# mm5823.net
KiCad netlist of a schematic drawn in EAGLE
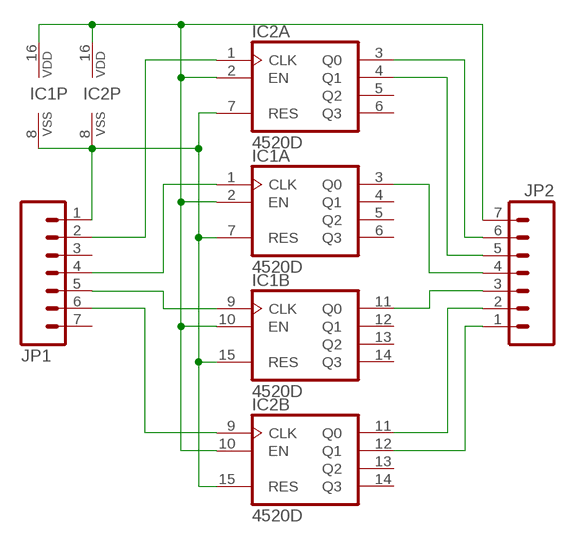
[diagram p0: schematic, sheet 1]

(export (version "E")
  (design (tool "Eeschema 10.0.6"))
  (components
    (comp (ref "IC1")
      (value "4520D")
      (footprint "eagle-import:SO16")
      (libsource (lib "eagle-import") (part "4520D"))
    )
    (comp (ref "IC2")
      (value "4520D")
      (footprint "eagle-import:SO16")
      (libsource (lib "eagle-import") (part "4520D"))
    )
    (comp (ref "JP1")
      (value "M07")
      (footprint "eagle-import:1X07")
      (libsource (lib "eagle-import") (part "M07"))
    )
    (comp (ref "JP2")
      (value "M07")
      (footprint "eagle-import:1X07")
      (libsource (lib "eagle-import") (part "M07"))
    )
  )
  (nets
    (net (code "1") (name "Net-(IC1A-CLK)") (class "Default")
      (node (ref "IC1") (pin "1") (pinfunction "CLK_1") (pintype "input"))
      (node (ref "JP1") (pin "4") (pinfunction "4_4") (pintype "passive"))
    )
    (net (code "2") (name "Net-(IC1A-EN)") (class "Default")
      (node (ref "IC1") (pin "10") (pinfunction "EN_10") (pintype "input"))
      (node (ref "IC1") (pin "16") (pinfunction "VDD_16") (pintype "power_in"))
      (node (ref "IC1") (pin "2") (pinfunction "EN_2") (pintype "input"))
      (node (ref "IC2") (pin "10") (pinfunction "EN_10") (pintype "input"))
      (node (ref "IC2") (pin "16") (pinfunction "VDD_16") (pintype "power_in"))
      (node (ref "IC2") (pin "2") (pinfunction "EN_2") (pintype "input"))
      (node (ref "JP2") (pin "7") (pinfunction "7_7") (pintype "passive"))
    )
    (net (code "3") (name "Net-(IC1A-Q0)") (class "Default")
      (node (ref "IC1") (pin "3") (pinfunction "Q0_3") (pintype "output"))
      (node (ref "JP2") (pin "4") (pinfunction "4_4") (pintype "passive"))
    )
    (net (code "4") (name "Net-(IC1A-RES)") (class "Default")
      (node (ref "IC1") (pin "15") (pinfunction "RES_15") (pintype "input"))
      (node (ref "IC1") (pin "7") (pinfunction "RES_7") (pintype "input"))
      (node (ref "IC1") (pin "8") (pinfunction "VSS_8") (pintype "power_in"))
      (node (ref "IC2") (pin "15") (pinfunction "RES_15") (pintype "input"))
      (node (ref "IC2") (pin "7") (pinfunction "RES_7") (pintype "input"))
      (node (ref "IC2") (pin "8") (pinfunction "VSS_8") (pintype "power_in"))
      (node (ref "JP1") (pin "1") (pinfunction "1_1") (pintype "passive"))
    )
    (net (code "5") (name "Net-(IC1B-CLK)") (class "Default")
      (node (ref "IC1") (pin "9") (pinfunction "CLK_9") (pintype "input"))
      (node (ref "JP1") (pin "5") (pinfunction "5_5") (pintype "passive"))
    )
    (net (code "6") (name "Net-(IC1B-Q0)") (class "Default")
      (node (ref "IC1") (pin "11") (pinfunction "Q0_11") (pintype "output"))
      (node (ref "JP2") (pin "3") (pinfunction "3_3") (pintype "passive"))
    )
    (net (code "7") (name "Net-(IC2A-CLK)") (class "Default")
      (node (ref "IC2") (pin "1") (pinfunction "CLK_1") (pintype "input"))
      (node (ref "JP1") (pin "2") (pinfunction "2_2") (pintype "passive"))
    )
    (net (code "8") (name "Net-(IC2A-Q0)") (class "Default")
      (node (ref "IC2") (pin "3") (pinfunction "Q0_3") (pintype "output"))
      (node (ref "JP2") (pin "6") (pinfunction "6_6") (pintype "passive"))
    )
    (net (code "9") (name "Net-(IC2A-Q1)") (class "Default")
      (node (ref "IC2") (pin "4") (pinfunction "Q1_4") (pintype "output"))
      (node (ref "JP2") (pin "5") (pinfunction "5_5") (pintype "passive"))
    )
    (net (code "10") (name "Net-(IC2B-CLK)") (class "Default")
      (node (ref "IC2") (pin "9") (pinfunction "CLK_9") (pintype "input"))
      (node (ref "JP1") (pin "6") (pinfunction "6_6") (pintype "passive"))
    )
    (net (code "11") (name "Net-(IC2B-Q0)") (class "Default")
      (node (ref "IC2") (pin "11") (pinfunction "Q0_11") (pintype "output"))
      (node (ref "JP2") (pin "2") (pinfunction "2_2") (pintype "passive"))
    )
    (net (code "12") (name "Net-(IC2B-Q1)") (class "Default")
      (node (ref "IC2") (pin "12") (pinfunction "Q1_12") (pintype "output"))
      (node (ref "JP2") (pin "1") (pinfunction "1_1") (pintype "passive"))
    )
    (net (code "13") (name "unconnected-(IC1A-Q1-Pad4)") (class "Default")
      (node (ref "IC1") (pin "4") (pinfunction "Q1_4") (pintype "output"))
    )
    (net (code "14") (name "unconnected-(IC1A-Q2-Pad5)") (class "Default")
      (node (ref "IC1") (pin "5") (pinfunction "Q2_5") (pintype "output"))
    )
    (net (code "15") (name "unconnected-(IC1A-Q3-Pad6)") (class "Default")
      (node (ref "IC1") (pin "6") (pinfunction "Q3_6") (pintype "output"))
    )
    (net (code "16") (name "unconnected-(IC1B-Q1-Pad12)") (class "Default")
      (node (ref "IC1") (pin "12") (pinfunction "Q1_12") (pintype "output"))
    )
    (net (code "17") (name "unconnected-(IC1B-Q2-Pad13)") (class "Default")
      (node (ref "IC1") (pin "13") (pinfunction "Q2_13") (pintype "output"))
    )
    (net (code "18") (name "unconnected-(IC1B-Q3-Pad14)") (class "Default")
      (node (ref "IC1") (pin "14") (pinfunction "Q3_14") (pintype "output"))
    )
    (net (code "19") (name "unconnected-(IC2A-Q2-Pad5)") (class "Default")
      (node (ref "IC2") (pin "5") (pinfunction "Q2_5") (pintype "output"))
    )
    (net (code "20") (name "unconnected-(IC2A-Q3-Pad6)") (class "Default")
      (node (ref "IC2") (pin "6") (pinfunction "Q3_6") (pintype "output"))
    )
    (net (code "21") (name "unconnected-(IC2B-Q2-Pad13)") (class "Default")
      (node (ref "IC2") (pin "13") (pinfunction "Q2_13") (pintype "output"))
    )
    (net (code "22") (name "unconnected-(IC2B-Q3-Pad14)") (class "Default")
      (node (ref "IC2") (pin "14") (pinfunction "Q3_14") (pintype "output"))
    )
    (net (code "23") (name "unconnected-(JP1-Pad3)") (class "Default")
      (node (ref "JP1") (pin "3") (pinfunction "3_3") (pintype "passive"))
    )
    (net (code "24") (name "unconnected-(JP1-Pad7)") (class "Default")
      (node (ref "JP1") (pin "7") (pinfunction "7_7") (pintype "passive"))
    )
  )
)
